# DVL_Interface.net
KiCad netlist of a schematic drawn in Altium Designer
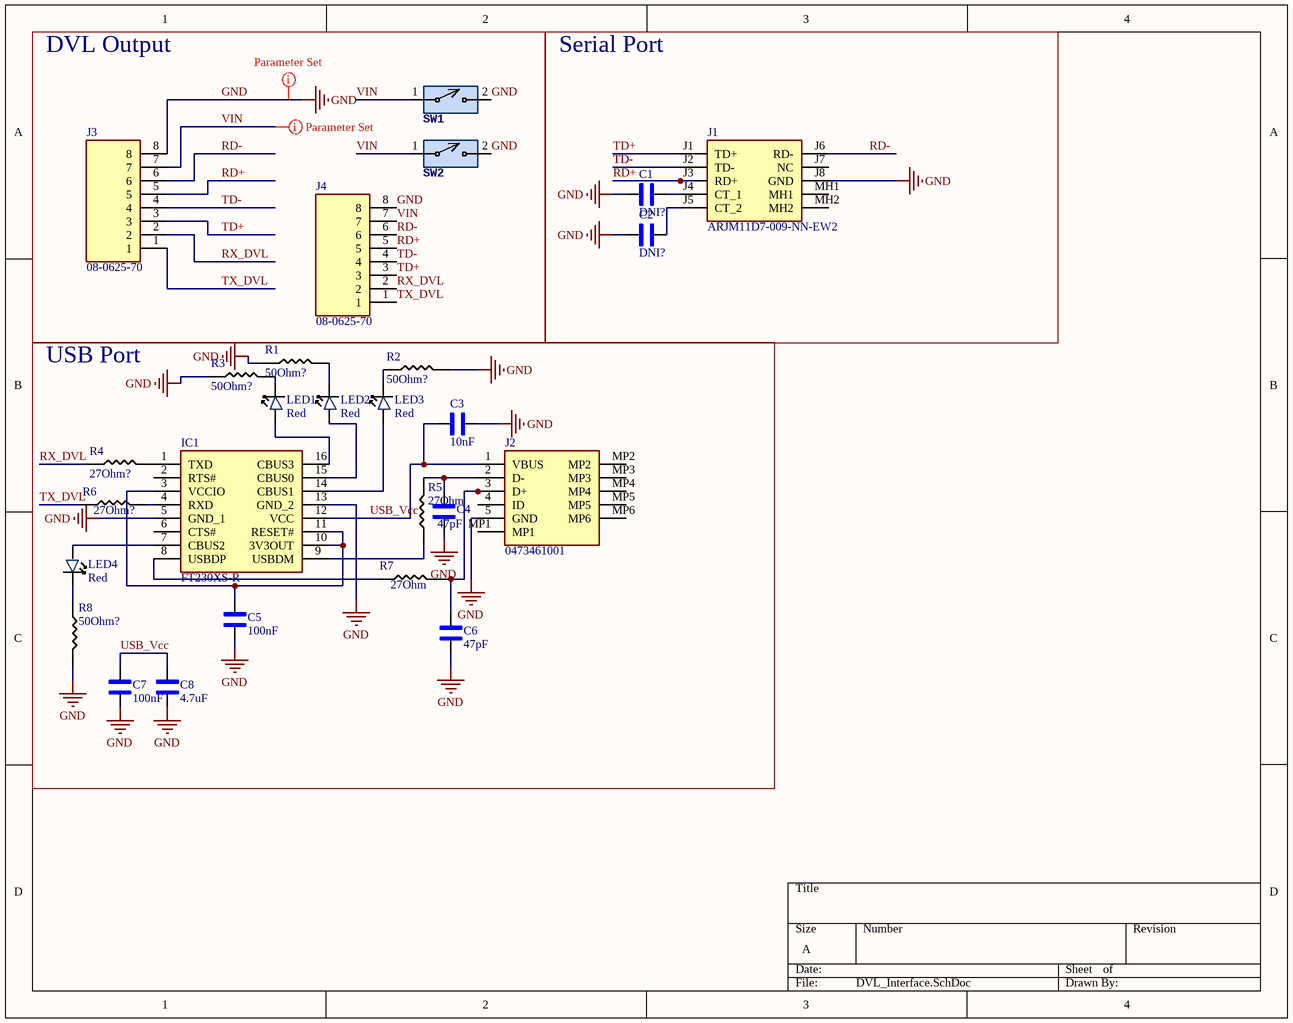
[diagram p0: DVL_Interface.SchDoc]

(export (version "E")
  (design (tool "Eeschema 10.0.6"))
  (components
    (comp (ref "C1")
      (value "DNI?")
      (footprint "1206_Passive_Capacitor")
      (description "10uF ±10% 50V X5R 1206 Multilayer Ceramic Capacitors MLCC - SMD/SMT RoHS")
      (fields (field (name "LCSC PART#") "C13585") (field (name "MFR PART #") "CL31A106KBHNNNE"))
      (libsource (lib "ECEN5730Lib_2023_05_DS") (part "C_10uF_1206"))
    )
    (comp (ref "C2")
      (value "DNI?")
      (footprint "1206_Passive_Capacitor")
      (description "10uF ±10% 50V X5R 1206 Multilayer Ceramic Capacitors MLCC - SMD/SMT RoHS")
      (fields (field (name "LCSC PART#") "C13585") (field (name "MFR PART #") "CL31A106KBHNNNE"))
      (libsource (lib "ECEN5730Lib_2023_05_DS") (part "C_10uF_1206"))
    )
    (comp (ref "C3")
      (value "10nF")
      (footprint "1206_Passive_Capacitor")
      (description "10uF ±10% 50V X5R 1206 Multilayer Ceramic Capacitors MLCC - SMD/SMT RoHS")
      (fields (field (name "LCSC PART#") "C13585") (field (name "MFR PART #") "CL31A106KBHNNNE"))
      (libsource (lib "ECEN5730Lib_2023_05_DS") (part "C_10uF_1206"))
    )
    (comp (ref "C4")
      (value "47pF")
      (footprint "1206_Passive_Capacitor")
      (description "47nF ±5% 50V C0G 1206 Multilayer Ceramic Capacitors MLCC - SMD/SMT RoHS")
      (fields (field (name "LCSC PART#") "C21812") (field (name "MFR PART #") "GRM31M5C1H473JA01L"))
      (libsource (lib "ECEN5730Lib_2023_05_DS") (part "C_47nF_1206"))
    )
    (comp (ref "C5")
      (value "100nF")
      (footprint "1206_Passive_Capacitor")
      (description "10uF ±10% 50V X5R 1206 Multilayer Ceramic Capacitors MLCC - SMD/SMT RoHS")
      (fields (field (name "LCSC PART#") "C13585") (field (name "MFR PART #") "CL31A106KBHNNNE"))
      (libsource (lib "ECEN5730Lib_2023_05_DS") (part "C_10uF_1206"))
    )
    (comp (ref "C6")
      (value "47pF")
      (footprint "1206_Passive_Capacitor")
      (description "47nF ±5% 50V C0G 1206 Multilayer Ceramic Capacitors MLCC - SMD/SMT RoHS")
      (fields (field (name "LCSC PART#") "C21812") (field (name "MFR PART #") "GRM31M5C1H473JA01L"))
      (libsource (lib "ECEN5730Lib_2023_05_DS") (part "C_47nF_1206"))
    )
    (comp (ref "C7")
      (value "100nF")
      (footprint "1206_Passive_Capacitor")
      (description "10uF ±10% 50V X5R 1206 Multilayer Ceramic Capacitors MLCC - SMD/SMT RoHS")
      (fields (field (name "LCSC PART#") "C13585") (field (name "MFR PART #") "CL31A106KBHNNNE"))
      (libsource (lib "ECEN5730Lib_2023_05_DS") (part "C_10uF_1206"))
    )
    (comp (ref "C8")
      (value "4.7uF")
      (footprint "1206_Passive_Capacitor")
      (description "10uF ±10% 50V X5R 1206 Multilayer Ceramic Capacitors MLCC - SMD/SMT RoHS")
      (fields (field (name "LCSC PART#") "C13585") (field (name "MFR PART #") "CL31A106KBHNNNE"))
      (libsource (lib "ECEN5730Lib_2023_05_DS") (part "C_10uF_1206"))
    )
    (comp (ref "IC1")
      (value "FT230XS-R")
      (footprint "SamacSys:SOP64P599X175-16N")
      (description "Integrated Circuit")
      (fields (field (name "MOUSER PART NUMBER") "895-FT230XS-R"))
      (libsource (lib "*") (part "FT230XS-R"))
    )
    (comp (ref "J1")
      (value "ARJM11D7-009-NN-EW2")
      (footprint "SamacSys:ARJM11D7009NNEW2")
      (description "Connector")
      (fields (field (name "MOUSER PART NUMBER") "815-RJM11D7009NNEW2"))
      (libsource (lib "*") (part "ARJM11D7-009-NN-EW2"))
    )
    (comp (ref "J2")
      (value "0473461001")
      (footprint "SamacSys:0473461001")
      (description "Connector")
      (libsource (lib "*") (part "0473461001"))
    )
    (comp (ref "J3")
      (value "08-0625-70")
      (footprint "SamacSys:HDRV8W51P0X254_1X8_2032X254X816P")
      (description "Connector")
      (fields (field (name "MOUSER PART NUMBER") "535-08-0625-70"))
      (libsource (lib "*") (part "08-0625-70"))
    )
    (comp (ref "J4")
      (value "08-0625-70")
      (footprint "SamacSys:HDRV8W51P0X254_1X8_2032X254X816P")
      (description "Connector")
      (fields (field (name "MOUSER PART NUMBER") "535-08-0625-70"))
      (libsource (lib "*") (part "08-0625-70"))
    )
    (comp (ref "LED1")
      (value "Red")
      (footprint "LED_1206")
      (description "Red 621~631nm 1206 Light Emitting Diodes (LED) RoHS")
      (fields (field (name "MFR PART #") "15-21/R6C-FQ1R1B/2T") (field (name "LCSC PART#") "C93133"))
      (libsource (lib "ECEN5730Lib_2023_05_DS") (part "LED_RED_1206"))
    )
    (comp (ref "LED2")
      (value "Red")
      (footprint "LED_1206")
      (description "Red 621~631nm 1206 Light Emitting Diodes (LED) RoHS")
      (fields (field (name "MFR PART #") "15-21/R6C-FQ1R1B/2T") (field (name "LCSC PART#") "C93133"))
      (libsource (lib "ECEN5730Lib_2023_05_DS") (part "LED_RED_1206"))
    )
    (comp (ref "LED3")
      (value "Red")
      (footprint "LED_1206")
      (description "Red 621~631nm 1206 Light Emitting Diodes (LED) RoHS")
      (fields (field (name "MFR PART #") "15-21/R6C-FQ1R1B/2T") (field (name "LCSC PART#") "C93133"))
      (libsource (lib "ECEN5730Lib_2023_05_DS") (part "LED_RED_1206"))
    )
    (comp (ref "LED4")
      (value "Red")
      (footprint "LED_1206")
      (description "Red 621~631nm 1206 Light Emitting Diodes (LED) RoHS")
      (fields (field (name "MFR PART #") "15-21/R6C-FQ1R1B/2T") (field (name "LCSC PART#") "C93133"))
      (libsource (lib "ECEN5730Lib_2023_05_DS") (part "LED_RED_1206"))
    )
    (comp (ref "R1")
      (value "50Ohm?")
      (footprint "1206_Passive_Resitor")
      (description "10 kOhms ±5% 0.25W, 1/4W Chip Resistor 1206 (3216 Metric) Automotive AEC-Q200 Thick Film")
      (fields (field (name "MFR PART #") "RMCF1206FT10K0") (field (name "LCSC PART#") "C17902"))
      (libsource (lib "ECEN5730Lib_2023_05_DS") (part "R_10KOhm_1206"))
    )
    (comp (ref "R2")
      (value "50Ohm?")
      (footprint "1206_Passive_Resitor")
      (description "10 kOhms ±5% 0.25W, 1/4W Chip Resistor 1206 (3216 Metric) Automotive AEC-Q200 Thick Film")
      (fields (field (name "MFR PART #") "RMCF1206FT10K0") (field (name "LCSC PART#") "C17902"))
      (libsource (lib "ECEN5730Lib_2023_05_DS") (part "R_10KOhm_1206"))
    )
    (comp (ref "R3")
      (value "50Ohm?")
      (footprint "1206_Passive_Resitor")
      (description "10 kOhms ±5% 0.25W, 1/4W Chip Resistor 1206 (3216 Metric) Automotive AEC-Q200 Thick Film")
      (fields (field (name "MFR PART #") "RMCF1206FT10K0") (field (name "LCSC PART#") "C17902"))
      (libsource (lib "ECEN5730Lib_2023_05_DS") (part "R_10KOhm_1206"))
    )
    (comp (ref "R4")
      (value "27Ohm?")
      (footprint "1206_Passive_Resitor")
      (description "10 kOhms ±5% 0.25W, 1/4W Chip Resistor 1206 (3216 Metric) Automotive AEC-Q200 Thick Film")
      (fields (field (name "MFR PART #") "RMCF1206FT10K0") (field (name "LCSC PART#") "C17902"))
      (libsource (lib "ECEN5730Lib_2023_05_DS") (part "R_10KOhm_1206"))
    )
    (comp (ref "R5")
      (value "27Ohm")
      (footprint "1206_Passive_Resitor")
      (description "CHIP RESISTOR - SURFACE MOUNT 22OHMS ±1% 1/4W 1206 ROHS")
      (fields (field (name "MFR PART #") "1206W4F220JT5E") (field (name "LCSC PART#") "C17958"))
      (libsource (lib "ECEN5730Lib_2023_05_DS") (part "R_22Ohm_1206"))
    )
    (comp (ref "R6")
      (value "27Ohm?")
      (footprint "1206_Passive_Resitor")
      (description "10 kOhms ±5% 0.25W, 1/4W Chip Resistor 1206 (3216 Metric) Automotive AEC-Q200 Thick Film")
      (fields (field (name "MFR PART #") "RMCF1206FT10K0") (field (name "LCSC PART#") "C17902"))
      (libsource (lib "ECEN5730Lib_2023_05_DS") (part "R_10KOhm_1206"))
    )
    (comp (ref "R7")
      (value "27Ohm")
      (footprint "1206_Passive_Resitor")
      (description "CHIP RESISTOR - SURFACE MOUNT 22OHMS ±1% 1/4W 1206 ROHS")
      (fields (field (name "MFR PART #") "1206W4F220JT5E") (field (name "LCSC PART#") "C17958"))
      (libsource (lib "ECEN5730Lib_2023_05_DS") (part "R_22Ohm_1206"))
    )
    (comp (ref "R8")
      (value "50Ohm?")
      (footprint "1206_Passive_Resitor")
      (description "10 kOhms ±5% 0.25W, 1/4W Chip Resistor 1206 (3216 Metric) Automotive AEC-Q200 Thick Film")
      (fields (field (name "MFR PART #") "RMCF1206FT10K0") (field (name "LCSC PART#") "C17902"))
      (libsource (lib "ECEN5730Lib_2023_05_DS") (part "R_10KOhm_1206"))
    )
    (comp (ref "SW1")
      (value "SW_2Pin_100mil_Switch")
      (footprint "2Pin-Header-Conn")
      (description "2Pin Header")
      (fields (field (name "LCSC PART#") "C124375"))
      (libsource (lib "ECEN5730Lib_2023_05_DS") (part "SW_2Pin_100mil_Switch"))
    )
    (comp (ref "SW2")
      (value "SW_2Pin_100mil_Switch")
      (footprint "2Pin-Header-Conn")
      (description "2Pin Header")
      (fields (field (name "LCSC PART#") "C124375"))
      (libsource (lib "ECEN5730Lib_2023_05_DS") (part "SW_2Pin_100mil_Switch"))
    )
  )
  (nets
    (net (code "1") (name "/RD+") (class "Default")
      (node (ref "J1") (pin "J3") (pinfunction "RD+_J3") (pintype "passive"))
      (node (ref "J3") (pin "5") (pinfunction "5_5") (pintype "passive"))
      (node (ref "J4") (pin "5") (pinfunction "5_5") (pintype "passive"))
    )
    (net (code "2") (name "/RD-") (class "Default")
      (node (ref "J1") (pin "J6") (pinfunction "RD-_J6") (pintype "passive"))
      (node (ref "J3") (pin "6") (pinfunction "6_6") (pintype "passive"))
      (node (ref "J4") (pin "6") (pinfunction "6_6") (pintype "passive"))
    )
    (net (code "3") (name "/RX_DVL") (class "Default")
      (node (ref "J3") (pin "2") (pinfunction "2_2") (pintype "passive"))
      (node (ref "J4") (pin "2") (pinfunction "2_2") (pintype "passive"))
      (node (ref "R4") (pin "1") (pinfunction "1_1") (pintype "passive"))
    )
    (net (code "4") (name "/TD+") (class "Default")
      (node (ref "J1") (pin "J1") (pinfunction "TD+_J1") (pintype "passive"))
      (node (ref "J3") (pin "3") (pinfunction "3_3") (pintype "passive"))
      (node (ref "J4") (pin "3") (pinfunction "3_3") (pintype "passive"))
    )
    (net (code "5") (name "/TD-") (class "Default")
      (node (ref "J1") (pin "J2") (pinfunction "TD-_J2") (pintype "passive"))
      (node (ref "J3") (pin "4") (pinfunction "4_4") (pintype "passive"))
      (node (ref "J4") (pin "4") (pinfunction "4_4") (pintype "passive"))
    )
    (net (code "6") (name "/TX_DVL") (class "Default")
      (node (ref "J3") (pin "1") (pinfunction "1_1") (pintype "passive"))
      (node (ref "J4") (pin "1") (pinfunction "1_1") (pintype "passive"))
      (node (ref "R6") (pin "1") (pinfunction "1_1") (pintype "passive"))
    )
    (net (code "7") (name "/USB_Vcc") (class "Default")
      (node (ref "C3") (pin "2") (pinfunction "2_2") (pintype "passive"))
      (node (ref "C7") (pin "2") (pinfunction "2_2") (pintype "passive"))
      (node (ref "C8") (pin "2") (pinfunction "2_2") (pintype "passive"))
      (node (ref "IC1") (pin "12") (pinfunction "VCC_12") (pintype "passive"))
      (node (ref "J2") (pin "1") (pinfunction "VBUS_1") (pintype "passive"))
    )
    (net (code "8") (name "/VIN") (class "Default")
      (node (ref "J3") (pin "7") (pinfunction "7_7") (pintype "passive"))
      (node (ref "J4") (pin "7") (pinfunction "7_7") (pintype "passive"))
      (node (ref "SW1") (pin "1") (pinfunction "1_1") (pintype "passive"))
      (node (ref "SW2") (pin "1") (pinfunction "1_1") (pintype "passive"))
    )
    (net (code "9") (name "GND") (class "Default")
      (node (ref "C1") (pin "2") (pinfunction "2_2") (pintype "passive"))
      (node (ref "C2") (pin "2") (pinfunction "2_2") (pintype "passive"))
      (node (ref "C3") (pin "1") (pinfunction "1_1") (pintype "passive"))
      (node (ref "C4") (pin "1") (pinfunction "1_1") (pintype "passive"))
      (node (ref "C5") (pin "1") (pinfunction "1_1") (pintype "passive"))
      (node (ref "C6") (pin "1") (pinfunction "1_1") (pintype "passive"))
      (node (ref "C7") (pin "1") (pinfunction "1_1") (pintype "passive"))
      (node (ref "C8") (pin "1") (pinfunction "1_1") (pintype "passive"))
      (node (ref "IC1") (pin "13") (pinfunction "GND_2_13") (pintype "passive"))
      (node (ref "IC1") (pin "5") (pinfunction "GND_1_5") (pintype "passive"))
      (node (ref "J1") (pin "J8") (pinfunction "GND_J8") (pintype "passive"))
      (node (ref "J2") (pin "5") (pinfunction "GND_5") (pintype "passive"))
      (node (ref "J3") (pin "8") (pinfunction "8_8") (pintype "passive"))
      (node (ref "J4") (pin "8") (pinfunction "8_8") (pintype "passive"))
      (node (ref "R1") (pin "1") (pinfunction "1_1") (pintype "passive"))
      (node (ref "R2") (pin "2") (pinfunction "2_2") (pintype "passive"))
      (node (ref "R3") (pin "1") (pinfunction "1_1") (pintype "passive"))
      (node (ref "R8") (pin "2") (pinfunction "2_2") (pintype "passive"))
      (node (ref "SW1") (pin "2") (pinfunction "2_2") (pintype "passive"))
      (node (ref "SW2") (pin "2") (pinfunction "2_2") (pintype "passive"))
    )
    (net (code "10") (name "Net-(IC1-3V3OUT)") (class "Default")
      (node (ref "C5") (pin "2") (pinfunction "2_2") (pintype "passive"))
      (node (ref "IC1") (pin "10") (pinfunction "3V3OUT_10") (pintype "passive"))
      (node (ref "IC1") (pin "11") (pinfunction "RESET#_11") (pintype "passive"))
      (node (ref "IC1") (pin "3") (pinfunction "VCCIO_3") (pintype "passive"))
    )
    (net (code "11") (name "Net-(IC1-CBUS0)") (class "Default")
      (node (ref "IC1") (pin "15") (pinfunction "CBUS0_15") (pintype "passive"))
      (node (ref "LED2") (pin "1") (pinfunction "1_1") (pintype "passive"))
    )
    (net (code "12") (name "Net-(IC1-CBUS1)") (class "Default")
      (node (ref "IC1") (pin "14") (pinfunction "CBUS1_14") (pintype "passive"))
      (node (ref "LED3") (pin "1") (pinfunction "1_1") (pintype "passive"))
    )
    (net (code "13") (name "Net-(IC1-CBUS2)") (class "Default")
      (node (ref "IC1") (pin "7") (pinfunction "CBUS2_7") (pintype "passive"))
      (node (ref "LED4") (pin "1") (pinfunction "1_1") (pintype "passive"))
    )
    (net (code "14") (name "Net-(IC1-CBUS3)") (class "Default")
      (node (ref "IC1") (pin "16") (pinfunction "CBUS3_16") (pintype "passive"))
      (node (ref "LED1") (pin "1") (pinfunction "1_1") (pintype "passive"))
    )
    (net (code "15") (name "Net-(IC1-RXD)") (class "Default")
      (node (ref "IC1") (pin "4") (pinfunction "RXD_4") (pintype "passive"))
      (node (ref "R6") (pin "2") (pinfunction "2_2") (pintype "passive"))
    )
    (net (code "16") (name "Net-(IC1-TXD)") (class "Default")
      (node (ref "IC1") (pin "1") (pinfunction "TXD_1") (pintype "passive"))
      (node (ref "R4") (pin "2") (pinfunction "2_2") (pintype "passive"))
    )
    (net (code "17") (name "Net-(IC1-USBDM)") (class "Default")
      (node (ref "IC1") (pin "9") (pinfunction "USBDM_9") (pintype "passive"))
      (node (ref "R5") (pin "1") (pinfunction "1_1") (pintype "passive"))
    )
    (net (code "18") (name "Net-(IC1-USBDP)") (class "Default")
      (node (ref "IC1") (pin "8") (pinfunction "USBDP_8") (pintype "passive"))
      (node (ref "R7") (pin "1") (pinfunction "1_1") (pintype "passive"))
    )
    (net (code "19") (name "Net-(J1-CT_1)") (class "Default")
      (node (ref "C1") (pin "1") (pinfunction "1_1") (pintype "passive"))
      (node (ref "J1") (pin "J4") (pinfunction "CT_1_J4") (pintype "passive"))
    )
    (net (code "20") (name "Net-(J1-CT_2)") (class "Default")
      (node (ref "C2") (pin "1") (pinfunction "1_1") (pintype "passive"))
      (node (ref "J1") (pin "J5") (pinfunction "CT_2_J5") (pintype "passive"))
    )
    (net (code "21") (name "Net-(J2-D+)") (class "Default")
      (node (ref "C6") (pin "2") (pinfunction "2_2") (pintype "passive"))
      (node (ref "J2") (pin "3") (pinfunction "D+_3") (pintype "passive"))
      (node (ref "R7") (pin "2") (pinfunction "2_2") (pintype "passive"))
    )
    (net (code "22") (name "Net-(J2-D-)") (class "Default")
      (node (ref "C4") (pin "2") (pinfunction "2_2") (pintype "passive"))
      (node (ref "J2") (pin "2") (pinfunction "D-_2") (pintype "passive"))
      (node (ref "R5") (pin "2") (pinfunction "2_2") (pintype "passive"))
    )
    (net (code "23") (name "Net-(LED1-Pad2)") (class "Default")
      (node (ref "LED1") (pin "2") (pinfunction "2_2") (pintype "passive"))
      (node (ref "R3") (pin "2") (pinfunction "2_2") (pintype "passive"))
    )
    (net (code "24") (name "Net-(LED2-Pad2)") (class "Default")
      (node (ref "LED2") (pin "2") (pinfunction "2_2") (pintype "passive"))
      (node (ref "R1") (pin "2") (pinfunction "2_2") (pintype "passive"))
    )
    (net (code "25") (name "Net-(LED3-Pad2)") (class "Default")
      (node (ref "LED3") (pin "2") (pinfunction "2_2") (pintype "passive"))
      (node (ref "R2") (pin "1") (pinfunction "1_1") (pintype "passive"))
    )
    (net (code "26") (name "Net-(LED4-Pad2)") (class "Default")
      (node (ref "LED4") (pin "2") (pinfunction "2_2") (pintype "passive"))
      (node (ref "R8") (pin "1") (pinfunction "1_1") (pintype "passive"))
    )
    (net (code "27") (name "unconnected-(IC1-CTS#-Pad6)") (class "Default")
      (node (ref "IC1") (pin "6") (pinfunction "CTS#_6") (pintype "passive"))
    )
    (net (code "28") (name "unconnected-(IC1-RTS#-Pad2)") (class "Default")
      (node (ref "IC1") (pin "2") (pinfunction "RTS#_2") (pintype "passive"))
    )
    (net (code "29") (name "unconnected-(J1-NC-PadJ7)") (class "Default")
      (node (ref "J1") (pin "J7") (pinfunction "NC_J7") (pintype "passive"))
    )
    (net (code "30") (name "unconnected-(J1-PadMH1)") (class "Default")
      (node (ref "J1") (pin "MH1") (pinfunction "MH1_MH1") (pintype "passive"))
    )
    (net (code "31") (name "unconnected-(J1-PadMH2)") (class "Default")
      (node (ref "J1") (pin "MH2") (pinfunction "MH2_MH2") (pintype "passive"))
    )
    (net (code "32") (name "unconnected-(J2-ID-Pad4)") (class "Default")
      (node (ref "J2") (pin "4") (pinfunction "ID_4") (pintype "passive"))
    )
    (net (code "33") (name "unconnected-(J2-PadMP1)") (class "Default")
      (node (ref "J2") (pin "MP1") (pinfunction "MP1_MP1") (pintype "passive"))
    )
    (net (code "34") (name "unconnected-(J2-PadMP2)") (class "Default")
      (node (ref "J2") (pin "MP2") (pinfunction "MP2_MP2") (pintype "passive"))
    )
    (net (code "35") (name "unconnected-(J2-PadMP3)") (class "Default")
      (node (ref "J2") (pin "MP3") (pinfunction "MP3_MP3") (pintype "passive"))
    )
    (net (code "36") (name "unconnected-(J2-PadMP4)") (class "Default")
      (node (ref "J2") (pin "MP4") (pinfunction "MP4_MP4") (pintype "passive"))
    )
    (net (code "37") (name "unconnected-(J2-PadMP5)") (class "Default")
      (node (ref "J2") (pin "MP5") (pinfunction "MP5_MP5") (pintype "passive"))
    )
    (net (code "38") (name "unconnected-(J2-PadMP6)") (class "Default")
      (node (ref "J2") (pin "MP6") (pinfunction "MP6_MP6") (pintype "passive"))
    )
  )
)
